# Vertap_UserInterface.net
KiCad netlist of a schematic drawn in Altium Designer
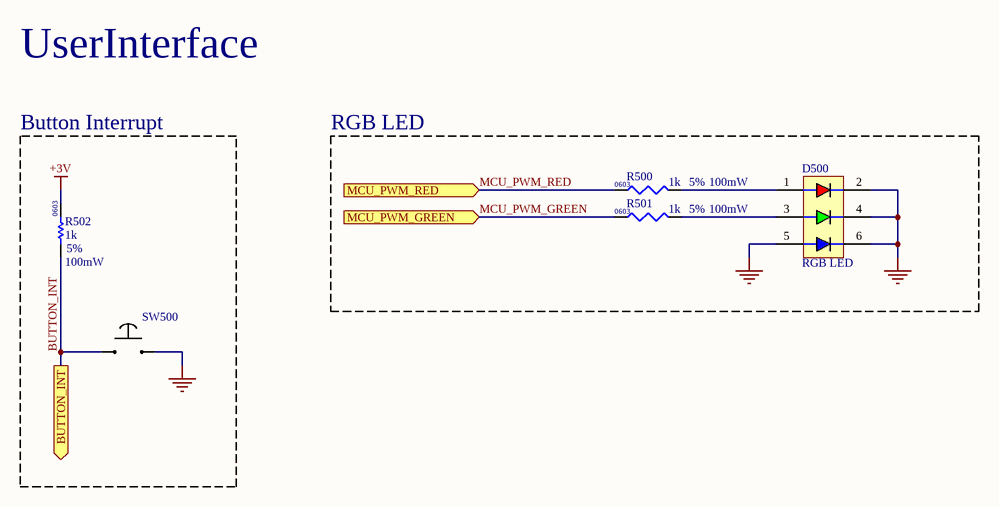
[diagram p0: Vertap_UserInterface.SchDoc]

(export (version "E")
  (design (tool "Eeschema 10.0.6"))
  (components
    (comp (ref "D500")
      (value "RGB LED")
      (footprint "ASMB-TTF0-0A20B")
      (libsource (lib "Vertap_SchLib") (part "ASMB-TTF0-0A20B"))
    )
    (comp (ref "R500")
      (value "1k")
      (footprint "RES_0603_YAGEO")
      (description "RES 1K OHM 5% 1/10W 0603")
      (fields
        (field (name "MANUFACTURER") "YAGEO")
        (field (name "MANUFACTURER PART NUMBER") "RC0603JR-101KL")
      )
      (libsource (lib "Vertap_SchLib") (part "RES_0603_1K"))
    )
    (comp (ref "R501")
      (value "1k")
      (footprint "RES_0603_YAGEO")
      (description "RES 1K OHM 5% 1/10W 0603")
      (fields
        (field (name "MANUFACTURER") "YAGEO")
        (field (name "MANUFACTURER PART NUMBER") "RC0603JR-101KL")
      )
      (libsource (lib "Vertap_SchLib") (part "RES_0603_1K"))
    )
    (comp (ref "R502")
      (value "1k")
      (footprint "RESC1608X55X25LL10T15")
      (fields (field (name "MANUFACTURER") "Yageo") (field (name "PART NUMBER") "RC0603JR-101KL"))
      (libsource (lib "Altium Content Vault") (part "RES"))
    )
    (comp (ref "SW500")
      (value "LS38G2F-T")
      (footprint "LS38G2F-T")
      (description "TOP-PRESS TACTILE SWITCH")
      (libsource (lib "Vertap_SchLib") (part "LS38G2F-T"))
    )
  )
  (nets
    (net (code "1") (name "+3V") (class "Default")
      (node (ref "R502") (pin "2") (pinfunction "2_2") (pintype "passive"))
    )
    (net (code "2") (name "/BUTTON_INT") (class "Default")
      (node (ref "R502") (pin "1") (pinfunction "1_1") (pintype "passive"))
      (node (ref "SW500") (pin "1") (pinfunction "0_1") (pintype "passive"))
    )
    (net (code "3") (name "/MCU_PWM_GREEN") (class "Default")
      (node (ref "R501") (pin "1") (pinfunction "1_1") (pintype "passive"))
    )
    (net (code "4") (name "/MCU_PWM_RED") (class "Default")
      (node (ref "R500") (pin "1") (pinfunction "1_1") (pintype "passive"))
    )
    (net (code "5") (name "GND") (class "Default")
      (node (ref "D500") (pin "2") (pinfunction "RED-_2") (pintype "passive"))
      (node (ref "D500") (pin "4") (pinfunction "GREEN-_4") (pintype "passive"))
      (node (ref "D500") (pin "5") (pinfunction "BLUE+_5") (pintype "passive"))
      (node (ref "D500") (pin "6") (pinfunction "BLUE-_6") (pintype "passive"))
      (node (ref "SW500") (pin "2") (pinfunction "1_2") (pintype "passive"))
    )
    (net (code "6") (name "Net-(D500-GREEN+)") (class "Default")
      (node (ref "D500") (pin "3") (pinfunction "GREEN+_3") (pintype "passive"))
      (node (ref "R501") (pin "2") (pinfunction "2_2") (pintype "passive"))
    )
    (net (code "7") (name "Net-(D500-RED+)") (class "Default")
      (node (ref "D500") (pin "1") (pinfunction "RED+_1") (pintype "passive"))
      (node (ref "R500") (pin "2") (pinfunction "2_2") (pintype "passive"))
    )
  )
)
